# DriverBoard.net
KiCad netlist of a schematic drawn in EAGLE
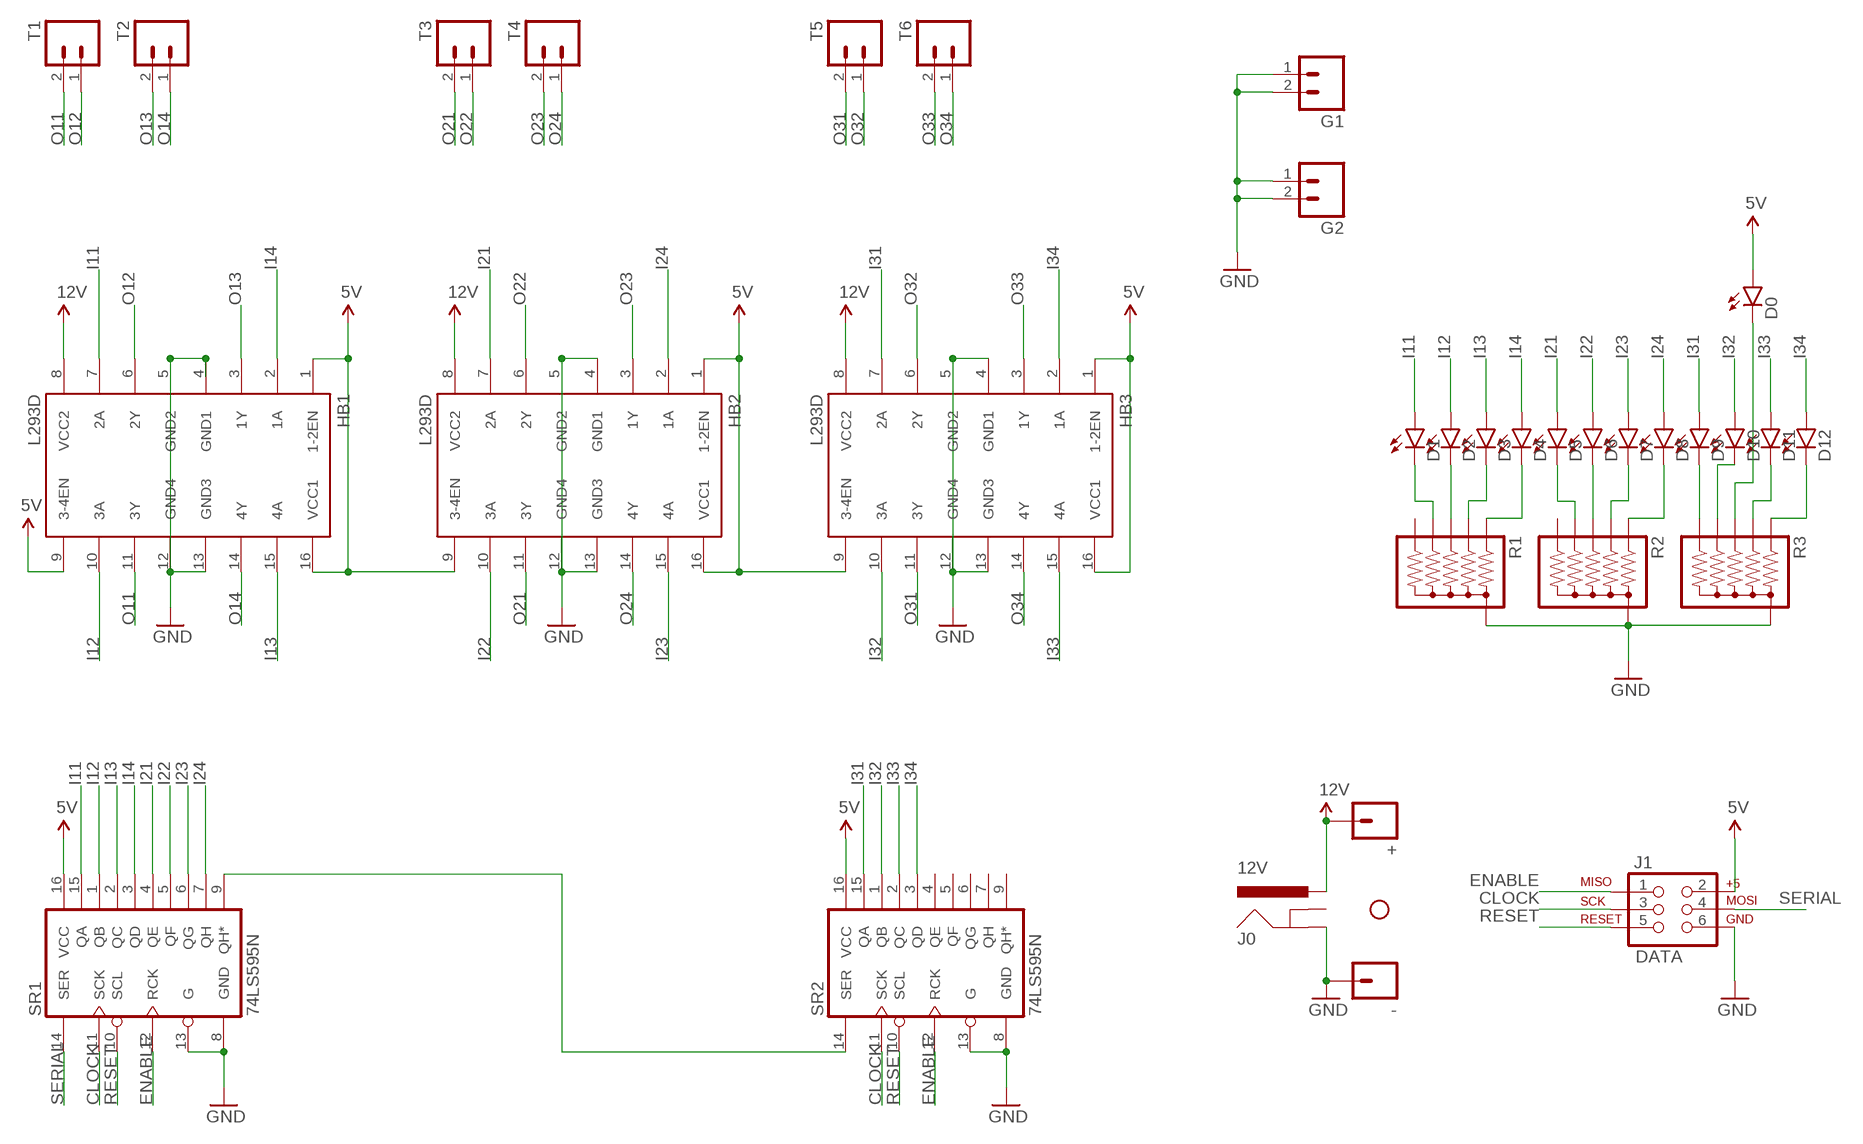
[diagram p0: schematic, sheet 1]

(export (version "E")
  (design (tool "Eeschema 10.0.6"))
  (components
    (comp (ref "+")
      (value "M01PTH_NO_SILK_YES_STOP")
      (footprint "eagle-import:1X01_NO_SILK")
      (libsource (lib "eagle-import") (part "M01PTH_NO_SILK_YES_STOP"))
    )
    (comp (ref "-")
      (value "M01PTH_NO_SILK_YES_STOP")
      (footprint "eagle-import:1X01_NO_SILK")
      (libsource (lib "eagle-import") (part "M01PTH_NO_SILK_YES_STOP"))
    )
    (comp (ref "D0")
      (value "LED5MM")
      (footprint "eagle-import:LED5MM")
      (libsource (lib "eagle-import") (part "LED5MM"))
    )
    (comp (ref "D1")
      (value "LED5MM")
      (footprint "eagle-import:LED5MM")
      (libsource (lib "eagle-import") (part "LED5MM"))
    )
    (comp (ref "D2")
      (value "LED5MM")
      (footprint "eagle-import:LED5MM")
      (libsource (lib "eagle-import") (part "LED5MM"))
    )
    (comp (ref "D3")
      (value "LED5MM")
      (footprint "eagle-import:LED5MM")
      (libsource (lib "eagle-import") (part "LED5MM"))
    )
    (comp (ref "D4")
      (value "LED5MM")
      (footprint "eagle-import:LED5MM")
      (libsource (lib "eagle-import") (part "LED5MM"))
    )
    (comp (ref "D5")
      (value "LED5MM")
      (footprint "eagle-import:LED5MM")
      (libsource (lib "eagle-import") (part "LED5MM"))
    )
    (comp (ref "D6")
      (value "LED5MM")
      (footprint "eagle-import:LED5MM")
      (libsource (lib "eagle-import") (part "LED5MM"))
    )
    (comp (ref "D7")
      (value "LED5MM")
      (footprint "eagle-import:LED5MM")
      (libsource (lib "eagle-import") (part "LED5MM"))
    )
    (comp (ref "D8")
      (value "LED5MM")
      (footprint "eagle-import:LED5MM")
      (libsource (lib "eagle-import") (part "LED5MM"))
    )
    (comp (ref "D9")
      (value "LED5MM")
      (footprint "eagle-import:LED5MM")
      (libsource (lib "eagle-import") (part "LED5MM"))
    )
    (comp (ref "D10")
      (value "LED5MM")
      (footprint "eagle-import:LED5MM")
      (libsource (lib "eagle-import") (part "LED5MM"))
    )
    (comp (ref "D11")
      (value "LED5MM")
      (footprint "eagle-import:LED5MM")
      (libsource (lib "eagle-import") (part "LED5MM"))
    )
    (comp (ref "D12")
      (value "LED5MM")
      (footprint "eagle-import:LED5MM")
      (libsource (lib "eagle-import") (part "LED5MM"))
    )
    (comp (ref "G1")
      (value "M025MM")
      (footprint "eagle-import:SCREWTERMINAL-5MM-2")
      (libsource (lib "eagle-import") (part "M025MM"))
    )
    (comp (ref "G2")
      (value "M025MM")
      (footprint "eagle-import:SCREWTERMINAL-5MM-2")
      (libsource (lib "eagle-import") (part "M025MM"))
    )
    (comp (ref "H1")
      (value "STAND-OFF")
      (footprint "eagle-import:STAND-OFF")
      (libsource (lib "eagle-import") (part "STAND-OFF"))
    )
    (comp (ref "HB1")
      (value "L293D")
      (footprint "eagle-import:DIL16")
      (libsource (lib "eagle-import") (part "L293D"))
    )
    (comp (ref "HB2")
      (value "L293D")
      (footprint "eagle-import:DIL16")
      (libsource (lib "eagle-import") (part "L293D"))
    )
    (comp (ref "HB3")
      (value "L293D")
      (footprint "eagle-import:DIL16")
      (libsource (lib "eagle-import") (part "L293D"))
    )
    (comp (ref "J0")
      (value "12V")
      (footprint "eagle-import:POWER_JACK_PTH_BREAD")
      (libsource (lib "eagle-import") (part "POWER_JACKPTH_BREAD"))
    )
    (comp (ref "J1")
      (value "DATA")
      (footprint "eagle-import:2X3")
      (libsource (lib "eagle-import") (part "AVR_SPI_PRG_6PTH"))
    )
    (comp (ref "R1")
      (value "RPACK-BUSSED-5-SIP-PTH-5")
      (footprint "eagle-import:RPACK-SIP-PTH-5")
      (libsource (lib "eagle-import") (part "RPACK-BUSSED-5-SIP-PTH-5"))
    )
    (comp (ref "R2")
      (value "RPACK-BUSSED-5-SIP-PTH-5")
      (footprint "eagle-import:RPACK-SIP-PTH-5")
      (libsource (lib "eagle-import") (part "RPACK-BUSSED-5-SIP-PTH-5"))
    )
    (comp (ref "R3")
      (value "RPACK-BUSSED-5-SIP-PTH-5")
      (footprint "eagle-import:RPACK-SIP-PTH-5")
      (libsource (lib "eagle-import") (part "RPACK-BUSSED-5-SIP-PTH-5"))
    )
    (comp (ref "SR1")
      (value "74LS595N")
      (footprint "eagle-import:DIL16")
      (libsource (lib "eagle-import") (part "74595NLS"))
    )
    (comp (ref "SR2")
      (value "74LS595N")
      (footprint "eagle-import:DIL16")
      (libsource (lib "eagle-import") (part "74595NLS"))
    )
    (comp (ref "T1")
      (value "M025MM")
      (footprint "eagle-import:SCREWTERMINAL-5MM-2")
      (libsource (lib "eagle-import") (part "M025MM"))
    )
    (comp (ref "T2")
      (value "M025MM")
      (footprint "eagle-import:SCREWTERMINAL-5MM-2")
      (libsource (lib "eagle-import") (part "M025MM"))
    )
    (comp (ref "T3")
      (value "M025MM")
      (footprint "eagle-import:SCREWTERMINAL-5MM-2")
      (libsource (lib "eagle-import") (part "M025MM"))
    )
    (comp (ref "T4")
      (value "M025MM")
      (footprint "eagle-import:SCREWTERMINAL-5MM-2")
      (libsource (lib "eagle-import") (part "M025MM"))
    )
    (comp (ref "T5")
      (value "M025MM")
      (footprint "eagle-import:SCREWTERMINAL-5MM-2")
      (libsource (lib "eagle-import") (part "M025MM"))
    )
    (comp (ref "T6")
      (value "M025MM")
      (footprint "eagle-import:SCREWTERMINAL-5MM-2")
      (libsource (lib "eagle-import") (part "M025MM"))
    )
  )
  (nets
    (net (code "1") (name "/CLOCK") (class "Default")
      (node (ref "J1") (pin "3") (pinfunction "3_3") (pintype "passive"))
      (node (ref "SR1") (pin "11") (pinfunction "SCK_11") (pintype "input"))
      (node (ref "SR2") (pin "11") (pinfunction "SCK_11") (pintype "input"))
    )
    (net (code "2") (name "/ENABLE") (class "Default")
      (node (ref "J1") (pin "1") (pinfunction "1_1") (pintype "passive"))
      (node (ref "SR1") (pin "12") (pinfunction "RCK_12") (pintype "input"))
      (node (ref "SR2") (pin "12") (pinfunction "RCK_12") (pintype "input"))
    )
    (net (code "3") (name "/I11") (class "Default")
      (node (ref "D1") (pin "A") (pinfunction "A_A") (pintype "passive"))
      (node (ref "HB1") (pin "7") (pinfunction "2A_7") (pintype "input"))
      (node (ref "SR1") (pin "15") (pinfunction "QA_15") (pintype "tri_state"))
    )
    (net (code "4") (name "/I12") (class "Default")
      (node (ref "D2") (pin "A") (pinfunction "A_A") (pintype "passive"))
      (node (ref "HB1") (pin "10") (pinfunction "3A_10") (pintype "input"))
      (node (ref "SR1") (pin "1") (pinfunction "QB_1") (pintype "tri_state"))
    )
    (net (code "5") (name "/I13") (class "Default")
      (node (ref "D3") (pin "A") (pinfunction "A_A") (pintype "passive"))
      (node (ref "HB1") (pin "15") (pinfunction "4A_15") (pintype "input"))
      (node (ref "SR1") (pin "2") (pinfunction "QC_2") (pintype "tri_state"))
    )
    (net (code "6") (name "/I14") (class "Default")
      (node (ref "D4") (pin "A") (pinfunction "A_A") (pintype "passive"))
      (node (ref "HB1") (pin "2") (pinfunction "1A_2") (pintype "input"))
      (node (ref "SR1") (pin "3") (pinfunction "QD_3") (pintype "tri_state"))
    )
    (net (code "7") (name "/I21") (class "Default")
      (node (ref "D5") (pin "A") (pinfunction "A_A") (pintype "passive"))
      (node (ref "HB2") (pin "7") (pinfunction "2A_7") (pintype "input"))
      (node (ref "SR1") (pin "4") (pinfunction "QE_4") (pintype "tri_state"))
    )
    (net (code "8") (name "/I22") (class "Default")
      (node (ref "D6") (pin "A") (pinfunction "A_A") (pintype "passive"))
      (node (ref "HB2") (pin "10") (pinfunction "3A_10") (pintype "input"))
      (node (ref "SR1") (pin "5") (pinfunction "QF_5") (pintype "tri_state"))
    )
    (net (code "9") (name "/I23") (class "Default")
      (node (ref "D7") (pin "A") (pinfunction "A_A") (pintype "passive"))
      (node (ref "HB2") (pin "15") (pinfunction "4A_15") (pintype "input"))
      (node (ref "SR1") (pin "6") (pinfunction "QG_6") (pintype "tri_state"))
    )
    (net (code "10") (name "/I24") (class "Default")
      (node (ref "D8") (pin "A") (pinfunction "A_A") (pintype "passive"))
      (node (ref "HB2") (pin "2") (pinfunction "1A_2") (pintype "input"))
      (node (ref "SR1") (pin "7") (pinfunction "QH_7") (pintype "tri_state"))
    )
    (net (code "11") (name "/I31") (class "Default")
      (node (ref "D9") (pin "A") (pinfunction "A_A") (pintype "passive"))
      (node (ref "HB3") (pin "7") (pinfunction "2A_7") (pintype "input"))
      (node (ref "SR2") (pin "15") (pinfunction "QA_15") (pintype "tri_state"))
    )
    (net (code "12") (name "/I32") (class "Default")
      (node (ref "D10") (pin "A") (pinfunction "A_A") (pintype "passive"))
      (node (ref "HB3") (pin "10") (pinfunction "3A_10") (pintype "input"))
      (node (ref "SR2") (pin "1") (pinfunction "QB_1") (pintype "tri_state"))
    )
    (net (code "13") (name "/I33") (class "Default")
      (node (ref "D11") (pin "A") (pinfunction "A_A") (pintype "passive"))
      (node (ref "HB3") (pin "15") (pinfunction "4A_15") (pintype "input"))
      (node (ref "SR2") (pin "2") (pinfunction "QC_2") (pintype "tri_state"))
    )
    (net (code "14") (name "/I34") (class "Default")
      (node (ref "D12") (pin "A") (pinfunction "A_A") (pintype "passive"))
      (node (ref "HB3") (pin "2") (pinfunction "1A_2") (pintype "input"))
      (node (ref "SR2") (pin "3") (pinfunction "QD_3") (pintype "tri_state"))
    )
    (net (code "15") (name "/O11") (class "Default")
      (node (ref "HB1") (pin "11") (pinfunction "3Y_11") (pintype "output"))
      (node (ref "T1") (pin "2") (pinfunction "2_2") (pintype "passive"))
    )
    (net (code "16") (name "/O12") (class "Default")
      (node (ref "HB1") (pin "6") (pinfunction "2Y_6") (pintype "output"))
      (node (ref "T1") (pin "1") (pinfunction "1_1") (pintype "passive"))
    )
    (net (code "17") (name "/O13") (class "Default")
      (node (ref "HB1") (pin "3") (pinfunction "1Y_3") (pintype "output"))
      (node (ref "T2") (pin "2") (pinfunction "2_2") (pintype "passive"))
    )
    (net (code "18") (name "/O14") (class "Default")
      (node (ref "HB1") (pin "14") (pinfunction "4Y_14") (pintype "output"))
      (node (ref "T2") (pin "1") (pinfunction "1_1") (pintype "passive"))
    )
    (net (code "19") (name "/O21") (class "Default")
      (node (ref "HB2") (pin "11") (pinfunction "3Y_11") (pintype "output"))
      (node (ref "T3") (pin "2") (pinfunction "2_2") (pintype "passive"))
    )
    (net (code "20") (name "/O22") (class "Default")
      (node (ref "HB2") (pin "6") (pinfunction "2Y_6") (pintype "output"))
      (node (ref "T3") (pin "1") (pinfunction "1_1") (pintype "passive"))
    )
    (net (code "21") (name "/O23") (class "Default")
      (node (ref "HB2") (pin "3") (pinfunction "1Y_3") (pintype "output"))
      (node (ref "T4") (pin "2") (pinfunction "2_2") (pintype "passive"))
    )
    (net (code "22") (name "/O24") (class "Default")
      (node (ref "HB2") (pin "14") (pinfunction "4Y_14") (pintype "output"))
      (node (ref "T4") (pin "1") (pinfunction "1_1") (pintype "passive"))
    )
    (net (code "23") (name "/O31") (class "Default")
      (node (ref "HB3") (pin "11") (pinfunction "3Y_11") (pintype "output"))
      (node (ref "T5") (pin "2") (pinfunction "2_2") (pintype "passive"))
    )
    (net (code "24") (name "/O32") (class "Default")
      (node (ref "HB3") (pin "6") (pinfunction "2Y_6") (pintype "output"))
      (node (ref "T5") (pin "1") (pinfunction "1_1") (pintype "passive"))
    )
    (net (code "25") (name "/O33") (class "Default")
      (node (ref "HB3") (pin "3") (pinfunction "1Y_3") (pintype "output"))
      (node (ref "T6") (pin "2") (pinfunction "2_2") (pintype "passive"))
    )
    (net (code "26") (name "/O34") (class "Default")
      (node (ref "HB3") (pin "14") (pinfunction "4Y_14") (pintype "output"))
      (node (ref "T6") (pin "1") (pinfunction "1_1") (pintype "passive"))
    )
    (net (code "27") (name "/RESET") (class "Default")
      (node (ref "J1") (pin "5") (pinfunction "5_5") (pintype "passive"))
      (node (ref "SR1") (pin "10") (pinfunction "SCL_10") (pintype "input"))
      (node (ref "SR2") (pin "10") (pinfunction "SCL_10") (pintype "input"))
    )
    (net (code "28") (name "/SERIAL") (class "Default")
      (node (ref "J1") (pin "4") (pinfunction "4_4") (pintype "passive"))
      (node (ref "SR1") (pin "14") (pinfunction "SER_14") (pintype "input"))
    )
    (net (code "29") (name "5V") (class "Default")
      (node (ref "D0") (pin "A") (pinfunction "A_A") (pintype "passive"))
      (node (ref "HB1") (pin "1") (pinfunction "1-2EN_1") (pintype "input"))
      (node (ref "HB1") (pin "16") (pinfunction "VCC1_16") (pintype "power_in"))
      (node (ref "HB1") (pin "9") (pinfunction "3-4EN_9") (pintype "input"))
      (node (ref "HB2") (pin "1") (pinfunction "1-2EN_1") (pintype "input"))
      (node (ref "HB2") (pin "16") (pinfunction "VCC1_16") (pintype "power_in"))
      (node (ref "HB2") (pin "9") (pinfunction "3-4EN_9") (pintype "input"))
      (node (ref "HB3") (pin "1") (pinfunction "1-2EN_1") (pintype "input"))
      (node (ref "HB3") (pin "16") (pinfunction "VCC1_16") (pintype "power_in"))
      (node (ref "HB3") (pin "9") (pinfunction "3-4EN_9") (pintype "input"))
      (node (ref "J1") (pin "2") (pinfunction "2_2") (pintype "passive"))
      (node (ref "SR1") (pin "16") (pinfunction "VCC_16") (pintype "power_in"))
      (node (ref "SR2") (pin "16") (pinfunction "VCC_16") (pintype "power_in"))
    )
    (net (code "30") (name "12V") (class "Default")
      (node (ref "+") (pin "1") (pinfunction "1_1") (pintype "passive"))
      (node (ref "HB1") (pin "8") (pinfunction "VCC2_8") (pintype "power_in"))
      (node (ref "HB2") (pin "8") (pinfunction "VCC2_8") (pintype "power_in"))
      (node (ref "HB3") (pin "8") (pinfunction "VCC2_8") (pintype "power_in"))
      (node (ref "J0") (pin "PWR") (pinfunction "PWR_PWR") (pintype "bidirectional"))
    )
    (net (code "31") (name "GND") (class "Default")
      (node (ref "-") (pin "1") (pinfunction "1_1") (pintype "passive"))
      (node (ref "G1") (pin "1") (pinfunction "1_1") (pintype "passive"))
      (node (ref "G1") (pin "2") (pinfunction "2_2") (pintype "passive"))
      (node (ref "G2") (pin "1") (pinfunction "1_1") (pintype "passive"))
      (node (ref "G2") (pin "2") (pinfunction "2_2") (pintype "passive"))
      (node (ref "HB1") (pin "12") (pinfunction "GND4_12") (pintype "power_in"))
      (node (ref "HB1") (pin "13") (pinfunction "GND3_13") (pintype "power_in"))
      (node (ref "HB1") (pin "4") (pinfunction "GND1_4") (pintype "power_in"))
      (node (ref "HB1") (pin "5") (pinfunction "GND2_5") (pintype "power_in"))
      (node (ref "HB2") (pin "12") (pinfunction "GND4_12") (pintype "power_in"))
      (node (ref "HB2") (pin "13") (pinfunction "GND3_13") (pintype "power_in"))
      (node (ref "HB2") (pin "4") (pinfunction "GND1_4") (pintype "power_in"))
      (node (ref "HB2") (pin "5") (pinfunction "GND2_5") (pintype "power_in"))
      (node (ref "HB3") (pin "12") (pinfunction "GND4_12") (pintype "power_in"))
      (node (ref "HB3") (pin "13") (pinfunction "GND3_13") (pintype "power_in"))
      (node (ref "HB3") (pin "4") (pinfunction "GND1_4") (pintype "power_in"))
      (node (ref "HB3") (pin "5") (pinfunction "GND2_5") (pintype "power_in"))
      (node (ref "J0") (pin "GND") (pinfunction "GND_GND") (pintype "bidirectional"))
      (node (ref "J1") (pin "6") (pinfunction "6_6") (pintype "passive"))
      (node (ref "R1") (pin "P$1") (pinfunction "1_P$1") (pintype "passive"))
      (node (ref "R2") (pin "P$1") (pinfunction "1_P$1") (pintype "passive"))
      (node (ref "R3") (pin "P$1") (pinfunction "1_P$1") (pintype "passive"))
      (node (ref "SR1") (pin "13") (pinfunction "G_13") (pintype "input"))
      (node (ref "SR1") (pin "8") (pinfunction "GND_8") (pintype "power_in"))
      (node (ref "SR2") (pin "13") (pinfunction "G_13") (pintype "input"))
      (node (ref "SR2") (pin "8") (pinfunction "GND_8") (pintype "power_in"))
    )
    (net (code "32") (name "Net-(D0-C)") (class "Default")
      (node (ref "D0") (pin "K") (pinfunction "C_K") (pintype "passive"))
      (node (ref "R3") (pin "P$4") (pinfunction "4_P$4") (pintype "passive"))
    )
    (net (code "33") (name "Net-(D1-C)") (class "Default")
      (node (ref "D1") (pin "K") (pinfunction "C_K") (pintype "passive"))
      (node (ref "R1") (pin "P$5") (pinfunction "5_P$5") (pintype "passive"))
    )
    (net (code "34") (name "Net-(D2-C)") (class "Default")
      (node (ref "D2") (pin "K") (pinfunction "C_K") (pintype "passive"))
      (node (ref "R1") (pin "P$4") (pinfunction "4_P$4") (pintype "passive"))
    )
    (net (code "35") (name "Net-(D3-C)") (class "Default")
      (node (ref "D3") (pin "K") (pinfunction "C_K") (pintype "passive"))
      (node (ref "R1") (pin "P$3") (pinfunction "3_P$3") (pintype "passive"))
    )
    (net (code "36") (name "Net-(D4-C)") (class "Default")
      (node (ref "D4") (pin "K") (pinfunction "C_K") (pintype "passive"))
      (node (ref "R1") (pin "P$2") (pinfunction "2_P$2") (pintype "passive"))
    )
    (net (code "37") (name "Net-(D5-C)") (class "Default")
      (node (ref "D5") (pin "K") (pinfunction "C_K") (pintype "passive"))
      (node (ref "R2") (pin "P$5") (pinfunction "5_P$5") (pintype "passive"))
    )
    (net (code "38") (name "Net-(D6-C)") (class "Default")
      (node (ref "D6") (pin "K") (pinfunction "C_K") (pintype "passive"))
      (node (ref "R2") (pin "P$4") (pinfunction "4_P$4") (pintype "passive"))
    )
    (net (code "39") (name "Net-(D7-C)") (class "Default")
      (node (ref "D7") (pin "K") (pinfunction "C_K") (pintype "passive"))
      (node (ref "R2") (pin "P$3") (pinfunction "3_P$3") (pintype "passive"))
    )
    (net (code "40") (name "Net-(D8-C)") (class "Default")
      (node (ref "D8") (pin "K") (pinfunction "C_K") (pintype "passive"))
      (node (ref "R2") (pin "P$2") (pinfunction "2_P$2") (pintype "passive"))
    )
    (net (code "41") (name "Net-(D9-C)") (class "Default")
      (node (ref "D9") (pin "K") (pinfunction "C_K") (pintype "passive"))
      (node (ref "R3") (pin "P$6") (pinfunction "6_P$6") (pintype "passive"))
    )
    (net (code "42") (name "Net-(D10-C)") (class "Default")
      (node (ref "D10") (pin "K") (pinfunction "C_K") (pintype "passive"))
      (node (ref "R3") (pin "P$5") (pinfunction "5_P$5") (pintype "passive"))
    )
    (net (code "43") (name "Net-(D11-C)") (class "Default")
      (node (ref "D11") (pin "K") (pinfunction "C_K") (pintype "passive"))
      (node (ref "R3") (pin "P$3") (pinfunction "3_P$3") (pintype "passive"))
    )
    (net (code "44") (name "Net-(D12-C)") (class "Default")
      (node (ref "D12") (pin "K") (pinfunction "C_K") (pintype "passive"))
      (node (ref "R3") (pin "P$2") (pinfunction "2_P$2") (pintype "passive"))
    )
    (net (code "45") (name "Net-(SR1-QH*)") (class "Default")
      (node (ref "SR1") (pin "9") (pinfunction "QH*_9") (pintype "tri_state"))
      (node (ref "SR2") (pin "14") (pinfunction "SER_14") (pintype "input"))
    )
    (net (code "46") (name "unconnected-(J0-PadGNDBREAK)") (class "Default")
      (node (ref "J0") (pin "GNDBREAK") (pinfunction "GNDBREAK_GNDBREAK") (pintype "bidirectional"))
    )
    (net (code "47") (name "unconnected-(R1-6-PadP$6)") (class "Default")
      (node (ref "R1") (pin "P$6") (pinfunction "6_P$6") (pintype "passive"))
    )
    (net (code "48") (name "unconnected-(R2-6-PadP$6)") (class "Default")
      (node (ref "R2") (pin "P$6") (pinfunction "6_P$6") (pintype "passive"))
    )
    (net (code "49") (name "unconnected-(SR2-QE-Pad4)") (class "Default")
      (node (ref "SR2") (pin "4") (pinfunction "QE_4") (pintype "tri_state"))
    )
    (net (code "50") (name "unconnected-(SR2-QF-Pad5)") (class "Default")
      (node (ref "SR2") (pin "5") (pinfunction "QF_5") (pintype "tri_state"))
    )
    (net (code "51") (name "unconnected-(SR2-QG-Pad6)") (class "Default")
      (node (ref "SR2") (pin "6") (pinfunction "QG_6") (pintype "tri_state"))
    )
    (net (code "52") (name "unconnected-(SR2-QH*-Pad9)") (class "Default")
      (node (ref "SR2") (pin "9") (pinfunction "QH*_9") (pintype "tri_state"))
    )
    (net (code "53") (name "unconnected-(SR2-QH-Pad7)") (class "Default")
      (node (ref "SR2") (pin "7") (pinfunction "QH_7") (pintype "tri_state"))
    )
  )
)
